# DP.net
KiCad netlist of a schematic drawn in Altium Designer
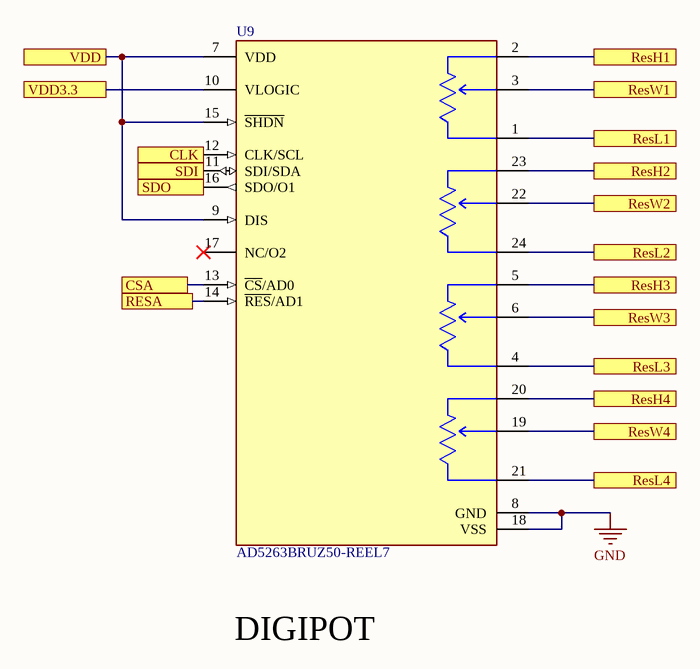
[diagram p0: DP.SchDoc]

(export (version "E")
  (design (tool "Eeschema 10.0.6"))
  (components
    (comp (ref "U9")
      (value "AD5263BRUZ50-REEL7")
      (footprint "FP-RU-24-IPC_A")
      (description "IC DGT POT 50KOHM 256TAP 24TSSOP")
      (fields (field (name "TOLERANCE") "30%"))
      (libsource (lib "Altium Content Vault") (part "8f750aaeae090b847826f69f71e761e"))
    )
  )
  (nets
    (net (code "1") (name "/CLK") (class "Default")
      (node (ref "U9") (pin "12") (pinfunction "CLK/SCL_12") (pintype "input"))
    )
    (net (code "2") (name "/CSA") (class "Default")
      (node (ref "U9") (pin "13") (pinfunction "~{CS}/AD0_13") (pintype "input"))
    )
    (net (code "3") (name "/RESA") (class "Default")
      (node (ref "U9") (pin "14") (pinfunction "~{RES}/AD1_14") (pintype "input"))
    )
    (net (code "4") (name "/ResH1") (class "Default")
      (node (ref "U9") (pin "2") (pinfunction "A1_2") (pintype "passive"))
    )
    (net (code "5") (name "/ResH2") (class "Default")
      (node (ref "U9") (pin "23") (pinfunction "A2_23") (pintype "passive"))
    )
    (net (code "6") (name "/ResH3") (class "Default")
      (node (ref "U9") (pin "5") (pinfunction "A3_5") (pintype "passive"))
    )
    (net (code "7") (name "/ResH4") (class "Default")
      (node (ref "U9") (pin "20") (pinfunction "A4_20") (pintype "passive"))
    )
    (net (code "8") (name "/ResL1") (class "Default")
      (node (ref "U9") (pin "1") (pinfunction "B1_1") (pintype "passive"))
    )
    (net (code "9") (name "/ResL2") (class "Default")
      (node (ref "U9") (pin "24") (pinfunction "B2_24") (pintype "passive"))
    )
    (net (code "10") (name "/ResL3") (class "Default")
      (node (ref "U9") (pin "4") (pinfunction "B3_4") (pintype "passive"))
    )
    (net (code "11") (name "/ResL4") (class "Default")
      (node (ref "U9") (pin "21") (pinfunction "B4_21") (pintype "passive"))
    )
    (net (code "12") (name "/ResW1") (class "Default")
      (node (ref "U9") (pin "3") (pinfunction "W1_3") (pintype "passive"))
    )
    (net (code "13") (name "/ResW2") (class "Default")
      (node (ref "U9") (pin "22") (pinfunction "W2_22") (pintype "passive"))
    )
    (net (code "14") (name "/ResW3") (class "Default")
      (node (ref "U9") (pin "6") (pinfunction "W3_6") (pintype "passive"))
    )
    (net (code "15") (name "/ResW4") (class "Default")
      (node (ref "U9") (pin "19") (pinfunction "W4_19") (pintype "passive"))
    )
    (net (code "16") (name "/SDI") (class "Default")
      (node (ref "U9") (pin "11") (pinfunction "SDI/SDA_11") (pintype "bidirectional"))
    )
    (net (code "17") (name "/SDO") (class "Default")
      (node (ref "U9") (pin "16") (pinfunction "SDO/O1_16") (pintype "output"))
    )
    (net (code "18") (name "/VDD") (class "Default")
      (node (ref "U9") (pin "15") (pinfunction "~{SHDN}_15") (pintype "input"))
      (node (ref "U9") (pin "7") (pinfunction "VDD_7") (pintype "power_in"))
      (node (ref "U9") (pin "9") (pinfunction "DIS_9") (pintype "input"))
    )
    (net (code "19") (name "/VDD3.3") (class "Default")
      (node (ref "U9") (pin "10") (pinfunction "VLOGIC_10") (pintype "power_in"))
    )
    (net (code "20") (name "GND") (class "Default")
      (node (ref "U9") (pin "18") (pinfunction "VSS_18") (pintype "power_in"))
      (node (ref "U9") (pin "8") (pinfunction "GND_8") (pintype "power_in"))
    )
    (net (code "21") (name "unconnected-(U9-NC{slash}O2-Pad17)") (class "Default")
      (node (ref "U9") (pin "17") (pinfunction "NC/O2_17") (pintype "passive+no_connect"))
    )
  )
)
